# 00_-_Power.net
KiCad netlist of a schematic drawn in Altium Designer
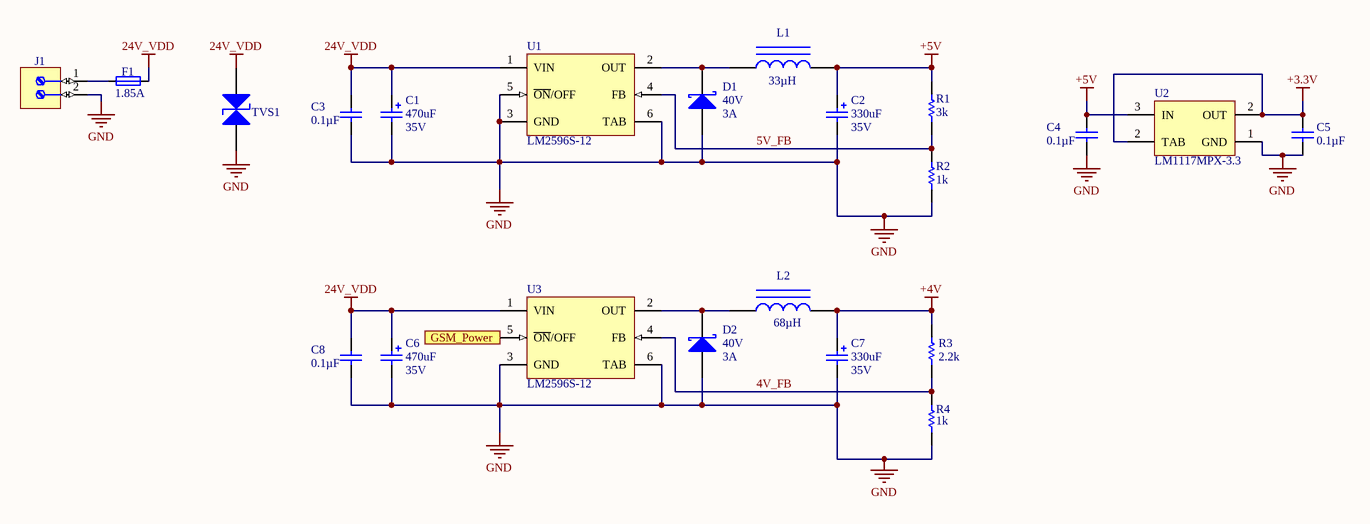
[diagram p0: [00] - Power.SchDoc]

(export (version "E")
  (design (tool "Eeschema 10.0.6"))
  (components
    (comp (ref "C1")
      (value "Capacitor Polarized")
      (footprint "Aluminium SMD G")
      (description "Aluminium SMD Capacitors")
      (fields
        (field (name "MANUFACTURER") "Nichicon")
        (field (name "MANUFACTURER PART NUMBER") "UCL1V471MNL1GS")
        (field (name "CAPACITANCE") "470uF")
        (field (name "VOLTAGE RATING") "35V")
      )
      (libsource (lib "Altium_Library") (part "Capacitor Polarized"))
    )
    (comp (ref "C2")
      (value "Capacitor Polarized")
      (footprint "Aluminium SMD G")
      (description "Aluminium SMD Capacitors")
      (fields
        (field (name "MANUFACTURER") "Panasonic")
        (field (name "MANUFACTURER PART NUMBER") "EEE-1VA331P")
        (field (name "CAPACITANCE") "330uF")
        (field (name "VOLTAGE") "35V")
      )
      (libsource (lib "Altium_Library") (part "Capacitor Polarized"))
    )
    (comp (ref "C3")
      (value "Capacitor")
      (footprint "Cap 0603")
      (description "Chip Capacitor Nonpolar")
      (fields
        (field (name "MANUFACTURER") "Kemet")
        (field (name "MANUFACTURER PART NUMBER") "C0603C104K5RACTU")
        (field (name "CAPACITANCE") "0.1µF")
      )
      (libsource (lib "Altium_Library") (part "Capacitor"))
    )
    (comp (ref "C4")
      (value "Capacitor")
      (footprint "Cap 0603")
      (description "Chip Capacitor Nonpolar")
      (fields
        (field (name "MANUFACTURER") "Kemet")
        (field (name "MANUFACTURER PART NUMBER") "C0603C104K5RACTU")
        (field (name "CAPACITANCE") "0.1µF")
      )
      (libsource (lib "Altium_Library") (part "Capacitor"))
    )
    (comp (ref "C5")
      (value "Capacitor")
      (footprint "Cap 0603")
      (description "Chip Capacitor Nonpolar")
      (fields
        (field (name "MANUFACTURER") "Kemet")
        (field (name "MANUFACTURER PART NUMBER") "C0603C104K5RACTU")
        (field (name "CAPACITANCE") "0.1µF")
      )
      (libsource (lib "Altium_Library") (part "Capacitor"))
    )
    (comp (ref "C6")
      (value "Capacitor Polarized")
      (footprint "Aluminium SMD G")
      (description "Aluminium SMD Capacitors")
      (fields
        (field (name "MANUFACTURER") "Nichicon")
        (field (name "MANUFACTURER PART NUMBER") "UCL1V471MNL1GS")
        (field (name "CAPACITANCE") "470uF")
        (field (name "VOLTAGE RATING") "35V")
      )
      (libsource (lib "Altium_Library") (part "Capacitor Polarized"))
    )
    (comp (ref "C7")
      (value "Capacitor Polarized")
      (footprint "Aluminium SMD G")
      (description "Aluminium SMD Capacitors")
      (fields
        (field (name "MANUFACTURER") "Panasonic")
        (field (name "MANUFACTURER PART NUMBER") "EEE-1VA331P")
        (field (name "CAPACITANCE") "330uF")
        (field (name "VOLTAGE") "35V")
      )
      (libsource (lib "Altium_Library") (part "Capacitor Polarized"))
    )
    (comp (ref "C8")
      (value "Capacitor")
      (footprint "Cap 0603")
      (description "Chip Capacitor Nonpolar")
      (fields
        (field (name "MANUFACTURER") "Kemet")
        (field (name "MANUFACTURER PART NUMBER") "C0603C104K5RACTU")
        (field (name "CAPACITANCE") "0.1µF")
      )
      (libsource (lib "Altium_Library") (part "Capacitor"))
    )
    (comp (ref "D1")
      (value "SK32")
      (footprint "SMA")
      (description "Schottky Rectifier")
      (fields
        (field (name "MANUFACTURER") "Diodes")
        (field (name "MANUFACTURER PART NUMBER") "B340A-13-F")
        (field (name "OUTPUT CURRENT") "3A")
        (field (name "VOLTAGE") "40V")
      )
      (libsource (lib "GSMInformer-PB-TC.v1.0-2013") (part "SK32"))
    )
    (comp (ref "D2")
      (value "SK32")
      (footprint "SMA")
      (description "Schottky Rectifier")
      (fields
        (field (name "MANUFACTURER") "Diodes")
        (field (name "MANUFACTURER PART NUMBER") "B340A-13-F")
        (field (name "OUTPUT CURRENT") "3A")
        (field (name "VOLTAGE") "40V")
      )
      (libsource (lib "GSMInformer-PB-TC.v1.0-2013") (part "SK32"))
    )
    (comp (ref "F1")
      (value "~")
      (footprint "FUSR_LITTELFUSE_2920L")
      (description "Fuse")
      (fields
        (field (name "MANUFACTURER") "Bel")
        (field (name "MANUFACTURER PART NUMBER") "0ZCF0185FF2C")
        (field (name "HOLD CURRENT") "1.85A")
        (field (name "AUTHOR") "CERN DEM JLC")
      )
      (libsource (lib "Eletro-mechanical") (part "Fuse"))
    )
    (comp (ref "J1")
      (value "~")
      (footprint "PHOENIX_1715721")
      (description "Terminal Block, 2 Positions, Screw Connection")
      (fields
        (field (name "PART NUMBER") "PHOENIX_1715721")
        (field (name "MANUFACTURER") "PHOENIX CONTACT")
        (field (name "AUTHOR") "CERN DEM JLC")
      )
      (libsource (lib "Connectors") (part "Terminal Block_2 Positions_Screw Connection"))
    )
    (comp (ref "L1")
      (value "SRR1210")
      (footprint "SRR1208")
      (description "Magnetic-Core Inductor")
      (fields
        (field (name "MANUFACTURER") "Bourns Inc.")
        (field (name "MANUFACTURER PART NUMBER") "SRR1208-330YL")
        (field (name "INDUCTANCE") "33µH")
      )
      (libsource (lib "GSMInformer-PB-TC.v1.0-2013") (part "SRR1210"))
    )
    (comp (ref "L2")
      (value "SRR1210")
      (footprint "SRR1208")
      (description "Magnetic-Core Inductor")
      (fields
        (field (name "MANUFACTURER") "Bourns Inc.")
        (field (name "MANUFACTURER PART NUMBER") "SRR1210-680M")
        (field (name "INDUCTANCE") "68µH")
        (field (name "PUBLISHER") "Altium Limited")
      )
      (libsource (lib "GSMInformer-PB-TC.v1.0-2013") (part "SRR1210"))
    )
    (comp (ref "R1")
      (value "Res1")
      (footprint "Res-0603")
      (description "Chip Resistor")
      (fields
        (field (name "MANUFACTURER") "Panasonic")
        (field (name "MANUFACTURER PART NUMBER") "ERJ-3GEYJ302V")
        (field (name "RESISTANCE") "3k")
      )
      (libsource (lib "Altium_Library") (part "Res1"))
    )
    (comp (ref "R2")
      (value "Res1")
      (footprint "Res-0603")
      (description "Chip Resistor")
      (fields
        (field (name "MANUFACTURER") "Panasonic")
        (field (name "MANUFACTURER PART NUMBER") "ERJ-3GEYJ102V")
        (field (name "RESISTANCE") "1k")
      )
      (libsource (lib "Altium_Library") (part "Res1"))
    )
    (comp (ref "R3")
      (value "Res1")
      (footprint "Res-0603")
      (description "Chip Resistor")
      (fields
        (field (name "MANUFACTURER") "Panasonic")
        (field (name "MANUFACTURER PART NUMBER") "ERJ-3GEYJ222V")
        (field (name "RESISTANCE") "2.2k")
      )
      (libsource (lib "Altium_Library") (part "Res1"))
    )
    (comp (ref "R4")
      (value "Res1")
      (footprint "Res-0603")
      (description "Chip Resistor")
      (fields
        (field (name "MANUFACTURER") "Panasonic")
        (field (name "MANUFACTURER PART NUMBER") "ERJ-3GEYJ102V")
        (field (name "RESISTANCE") "1k")
      )
      (libsource (lib "Altium_Library") (part "Res1"))
    )
    (comp (ref "TVS1")
      (value "TVS")
      (footprint "DO-201A")
      (description "TVS DIODE 30.8VWM 64.3VC DO201")
      (fields
        (field (name "MANUFACTURER") "STMicroelectronics")
        (field (name "MANUFACTURER PART NUMBER") "1.5KE36A")
      )
      (libsource (lib "Altium_Library") (part "TVS"))
    )
    (comp (ref "U1")
      (value "LM2596S-12")
      (footprint "TS5B_M")
      (description "SIMPLE SWITCHER® Power Converter 150 KHz 3A Step-Down Voltage Regulator, 5-pin TO-263")
      (fields
        (field (name "MANUFACTURER") "TI National Semiconductor")
        (field (name "MANUFACTURER PART NUMBER") "LM2596S-12/NOPB")
      )
      (libsource (lib "NSC Switcher") (part "LM2596S-12"))
    )
    (comp (ref "U2")
      (value "LM1117MPX-3.3")
      (footprint "SOT-223")
      (description "800mA Low-Dropout Linear Regulator, 4-pin SOT-223")
      (fields
        (field (name "MANUFACTURER") "Texas Instruments")
        (field (name "MANUFACTURER PART NUMBER") "LM1117MPX-3.3/NOPB")
      )
      (libsource (lib "NSC LDO") (part "LM1117MPX-3.3"))
    )
    (comp (ref "U3")
      (value "LM2596S-12")
      (footprint "TS5B_M")
      (description "SIMPLE SWITCHER® Power Converter 150 KHz 3A Step-Down Voltage Regulator, 5-pin TO-263")
      (fields
        (field (name "MANUFACTURER") "TI National Semiconductor")
        (field (name "MANUFACTURER PART NUMBER") "LM2596S-12/NOPB")
      )
      (libsource (lib "NSC Switcher") (part "LM2596S-12"))
    )
  )
  (nets
    (net (code "1") (name "+3.3V") (class "Default")
      (node (ref "C5") (pin "2") (pinfunction "2_2") (pintype "passive"))
      (node (ref "U2") (pin "2") (pinfunction "TAB_2") (pintype "power_in"))
    )
    (net (code "2") (name "+4V") (class "Default")
      (node (ref "C7") (pin "1") (pinfunction "1_1") (pintype "passive"))
      (node (ref "L2") (pin "2") (pinfunction "2_2") (pintype "passive"))
      (node (ref "R3") (pin "1") (pinfunction "1_1") (pintype "passive"))
    )
    (net (code "3") (name "+5V") (class "Default")
      (node (ref "C2") (pin "1") (pinfunction "1_1") (pintype "passive"))
      (node (ref "C4") (pin "2") (pinfunction "2_2") (pintype "passive"))
      (node (ref "L1") (pin "2") (pinfunction "2_2") (pintype "passive"))
      (node (ref "R1") (pin "2") (pinfunction "2_2") (pintype "passive"))
      (node (ref "U2") (pin "3") (pinfunction "IN_3") (pintype "power_in"))
    )
    (net (code "4") (name "/4V_FB") (class "Default")
      (node (ref "R3") (pin "2") (pinfunction "2_2") (pintype "passive"))
      (node (ref "R4") (pin "2") (pinfunction "2_2") (pintype "passive"))
      (node (ref "U3") (pin "4") (pinfunction "FB_4") (pintype "input"))
    )
    (net (code "5") (name "/5V_FB") (class "Default")
      (node (ref "R1") (pin "1") (pinfunction "1_1") (pintype "passive"))
      (node (ref "R2") (pin "2") (pinfunction "2_2") (pintype "passive"))
      (node (ref "U1") (pin "4") (pinfunction "FB_4") (pintype "input"))
    )
    (net (code "6") (name "/GSM_Power") (class "Default")
      (node (ref "U3") (pin "5") (pinfunction "~{ON}/OFF_5") (pintype "input"))
    )
    (net (code "7") (name "24V_VDD") (class "Default")
      (node (ref "C1") (pin "1") (pinfunction "1_1") (pintype "passive"))
      (node (ref "C3") (pin "2") (pinfunction "2_2") (pintype "passive"))
      (node (ref "C6") (pin "1") (pinfunction "1_1") (pintype "passive"))
      (node (ref "C8") (pin "2") (pinfunction "2_2") (pintype "passive"))
      (node (ref "F1") (pin "2") (pinfunction "2_2") (pintype "passive"))
      (node (ref "TVS1") (pin "1") (pinfunction "A_1") (pintype "passive"))
      (node (ref "U1") (pin "1") (pinfunction "VIN_1") (pintype "power_in"))
      (node (ref "U3") (pin "1") (pinfunction "VIN_1") (pintype "power_in"))
    )
    (net (code "8") (name "GND") (class "Default")
      (node (ref "C1") (pin "2") (pinfunction "2_2") (pintype "passive"))
      (node (ref "C2") (pin "2") (pinfunction "2_2") (pintype "passive"))
      (node (ref "C3") (pin "1") (pinfunction "1_1") (pintype "passive"))
      (node (ref "C4") (pin "1") (pinfunction "1_1") (pintype "passive"))
      (node (ref "C5") (pin "1") (pinfunction "1_1") (pintype "passive"))
      (node (ref "C6") (pin "2") (pinfunction "2_2") (pintype "passive"))
      (node (ref "C7") (pin "2") (pinfunction "2_2") (pintype "passive"))
      (node (ref "C8") (pin "1") (pinfunction "1_1") (pintype "passive"))
      (node (ref "D1") (pin "1") (pinfunction "A_1") (pintype "passive"))
      (node (ref "D2") (pin "1") (pinfunction "A_1") (pintype "passive"))
      (node (ref "J1") (pin "2") (pinfunction "2_2") (pintype "bidirectional"))
      (node (ref "R2") (pin "1") (pinfunction "1_1") (pintype "passive"))
      (node (ref "R4") (pin "1") (pinfunction "1_1") (pintype "passive"))
      (node (ref "TVS1") (pin "2") (pinfunction "K_2") (pintype "passive"))
      (node (ref "U1") (pin "3") (pinfunction "GND_3") (pintype "power_in"))
      (node (ref "U1") (pin "5") (pinfunction "~{ON}/OFF_5") (pintype "input"))
      (node (ref "U1") (pin "6") (pinfunction "TAB_6") (pintype "power_in"))
      (node (ref "U2") (pin "1") (pinfunction "GND_1") (pintype "power_in"))
      (node (ref "U3") (pin "3") (pinfunction "GND_3") (pintype "power_in"))
      (node (ref "U3") (pin "6") (pinfunction "TAB_6") (pintype "power_in"))
    )
    (net (code "9") (name "Net-(D1-K)") (class "Default")
      (node (ref "D1") (pin "2") (pinfunction "K_2") (pintype "passive"))
      (node (ref "L1") (pin "1") (pinfunction "1_1") (pintype "passive"))
      (node (ref "U1") (pin "2") (pinfunction "OUT_2") (pintype "power_in"))
    )
    (net (code "10") (name "Net-(D2-K)") (class "Default")
      (node (ref "D2") (pin "2") (pinfunction "K_2") (pintype "passive"))
      (node (ref "L2") (pin "1") (pinfunction "1_1") (pintype "passive"))
      (node (ref "U3") (pin "2") (pinfunction "OUT_2") (pintype "power_in"))
    )
    (net (code "11") (name "Net-(F1-Pad1)") (class "Default")
      (node (ref "F1") (pin "1") (pinfunction "1_1") (pintype "passive"))
      (node (ref "J1") (pin "1") (pinfunction "1_1") (pintype "bidirectional"))
    )
  )
)
